# BMS_VSNS.net
KiCad netlist of a schematic drawn in Altium Designer
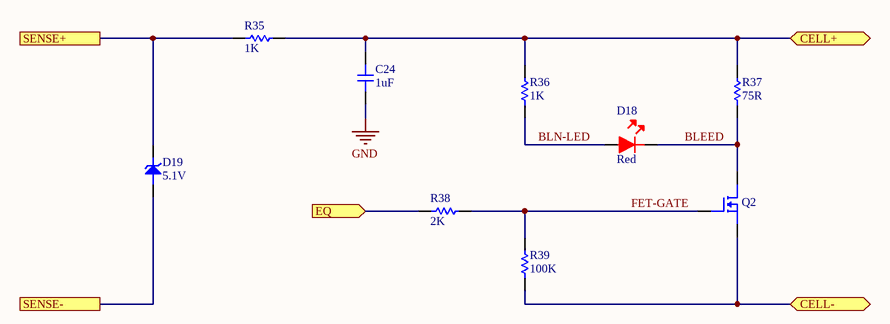
[diagram p0: BMS_VSNS.SchDoc]

(export (version "E")
  (design (tool "Eeschema 10.0.6"))
  (components
    (comp (ref "C24")
      (value "1uF")
      (footprint "CAP-0603")
      (description "CAP CER 1UF 16V X7R 0603")
      (fields
        (field (name "MANUFACTURER") "KEMET")
        (field (name "MANUFACTURER PART NUMBER") "C0603C105K4RACTU")
      )
      (libsource (lib "Capacitors") (part "0603-1uF-16V"))
    )
    (comp (ref "D18")
      (value "Red")
      (footprint "LED-0603")
      (description "LED RED CLEAR 0603 SMD")
      (fields
        (field (name "MANUFACTURER") "Wurth Electronics")
        (field (name "MANUFACTURER PART NUMBER") "150060RS75000")
      )
      (libsource (lib "LEDs") (part "LED-Red"))
    )
    (comp (ref "D19")
      (value "5.1V")
      (footprint "DIODE-SOD123")
      (description "DIODE ZENER 5.1V 500MW SOD123")
      (fields (field (name "MANUFACTURER") "MCC") (field (name "MANUFACTURER PART NUMBER") "MMSZ4689-TP"))
      (libsource (lib "Diodes") (part "Zener-5.1V-0.5W"))
    )
    (comp (ref "Q2")
      (value "DMN6140L-13DICT-ND")
      (footprint "SOT-23-3")
      (description "MOSFET N-CH 60V 1.6A SOT23")
      (fields (field (name "MANUFACTURER") "Diodes") (field (name "MANUFACTURER PART NUMBER") "DMN6140L-13"))
      (libsource (lib "Transistors") (part "N-FET-60V-1.6A"))
    )
    (comp (ref "R35")
      (value "1K")
      (footprint "RES-0603")
      (description "RES SMD 1K OHM 1% 1/10W 0603")
      (fields
        (field (name "MANUFACTURER") "Vishay Dale")
        (field (name "MANUFACTURER PART NUMBER") "CRCW06031K00FKEA")
      )
      (libsource (lib "Resistors") (part "0603-1KR"))
    )
    (comp (ref "R36")
      (value "1K")
      (footprint "RES-0603")
      (description "RES SMD 1K OHM 1% 1/10W 0603")
      (fields
        (field (name "MANUFACTURER") "Vishay Dale")
        (field (name "MANUFACTURER PART NUMBER") "CRCW06031K00FKEA")
      )
      (libsource (lib "Resistors") (part "0603-1KR"))
    )
    (comp (ref "R37")
      (value "75R")
      (footprint "RES-2512")
      (description "RES 75 OHM 1% 1W 2512")
      (fields
        (field (name "MANUFACTURER") "Stackpole Electronics")
        (field (name "MANUFACTURER PART NUMBER") "RMCF2512FT75R0")
      )
      (libsource (lib "Resistors") (part "2512-75R"))
    )
    (comp (ref "R38")
      (value "2K")
      (footprint "RES-0603")
      (description "RES SMD 2K OHM 1% 1/4W 0603")
      (fields
        (field (name "MANUFACTURER") "Vishay Dale")
        (field (name "MANUFACTURER PART NUMBER") "CRCW06032K00FKEAHP")
      )
      (libsource (lib "Resistors") (part "0603-2KR"))
    )
    (comp (ref "R39")
      (value "100K")
      (footprint "RES-0603")
      (description "RES 100K OHM 1% 1/10W 0603")
      (fields
        (field (name "MANUFACTURER") "Stackpole Electronics")
        (field (name "MANUFACTURER PART NUMBER") "RMCF0603FT100K")
      )
      (libsource (lib "Resistors") (part "0603-100KR"))
    )
  )
  (nets
    (net (code "1") (name "/BLEED") (class "Default")
      (node (ref "D18") (pin "2") (pinfunction "2_2") (pintype "passive"))
      (node (ref "Q2") (pin "2") (pinfunction "2_2") (pintype "passive"))
      (node (ref "R37") (pin "1") (pinfunction "1_1") (pintype "passive"))
    )
    (net (code "2") (name "/BLN-LED") (class "Default")
      (node (ref "D18") (pin "1") (pinfunction "1_1") (pintype "passive"))
      (node (ref "R36") (pin "1") (pinfunction "1_1") (pintype "passive"))
    )
    (net (code "3") (name "/CELL+") (class "Default")
      (node (ref "C24") (pin "2") (pinfunction "2_2") (pintype "passive"))
      (node (ref "R35") (pin "2") (pinfunction "2_2") (pintype "passive"))
      (node (ref "R36") (pin "2") (pinfunction "2_2") (pintype "passive"))
      (node (ref "R37") (pin "2") (pinfunction "2_2") (pintype "passive"))
    )
    (net (code "4") (name "/CELL-") (class "Default")
      (node (ref "Q2") (pin "3") (pinfunction "3_3") (pintype "passive"))
      (node (ref "R39") (pin "1") (pinfunction "1_1") (pintype "passive"))
    )
    (net (code "5") (name "/EQ") (class "Default")
      (node (ref "R38") (pin "1") (pinfunction "1_1") (pintype "passive"))
    )
    (net (code "6") (name "/FET-GATE") (class "Default")
      (node (ref "Q2") (pin "1") (pinfunction "1_1") (pintype "passive"))
      (node (ref "R38") (pin "2") (pinfunction "2_2") (pintype "passive"))
      (node (ref "R39") (pin "2") (pinfunction "2_2") (pintype "passive"))
    )
    (net (code "7") (name "/SENSE+") (class "Default")
      (node (ref "D19") (pin "1") (pinfunction "1_1") (pintype "passive"))
      (node (ref "R35") (pin "1") (pinfunction "1_1") (pintype "passive"))
    )
    (net (code "8") (name "/SENSE-") (class "Default")
      (node (ref "D19") (pin "2") (pinfunction "2_2") (pintype "passive"))
    )
    (net (code "9") (name "GND") (class "Default")
      (node (ref "C24") (pin "1") (pinfunction "1_1") (pintype "passive"))
    )
  )
)
